# design.net
KiCad netlist of a schematic drawn in Altium Designer
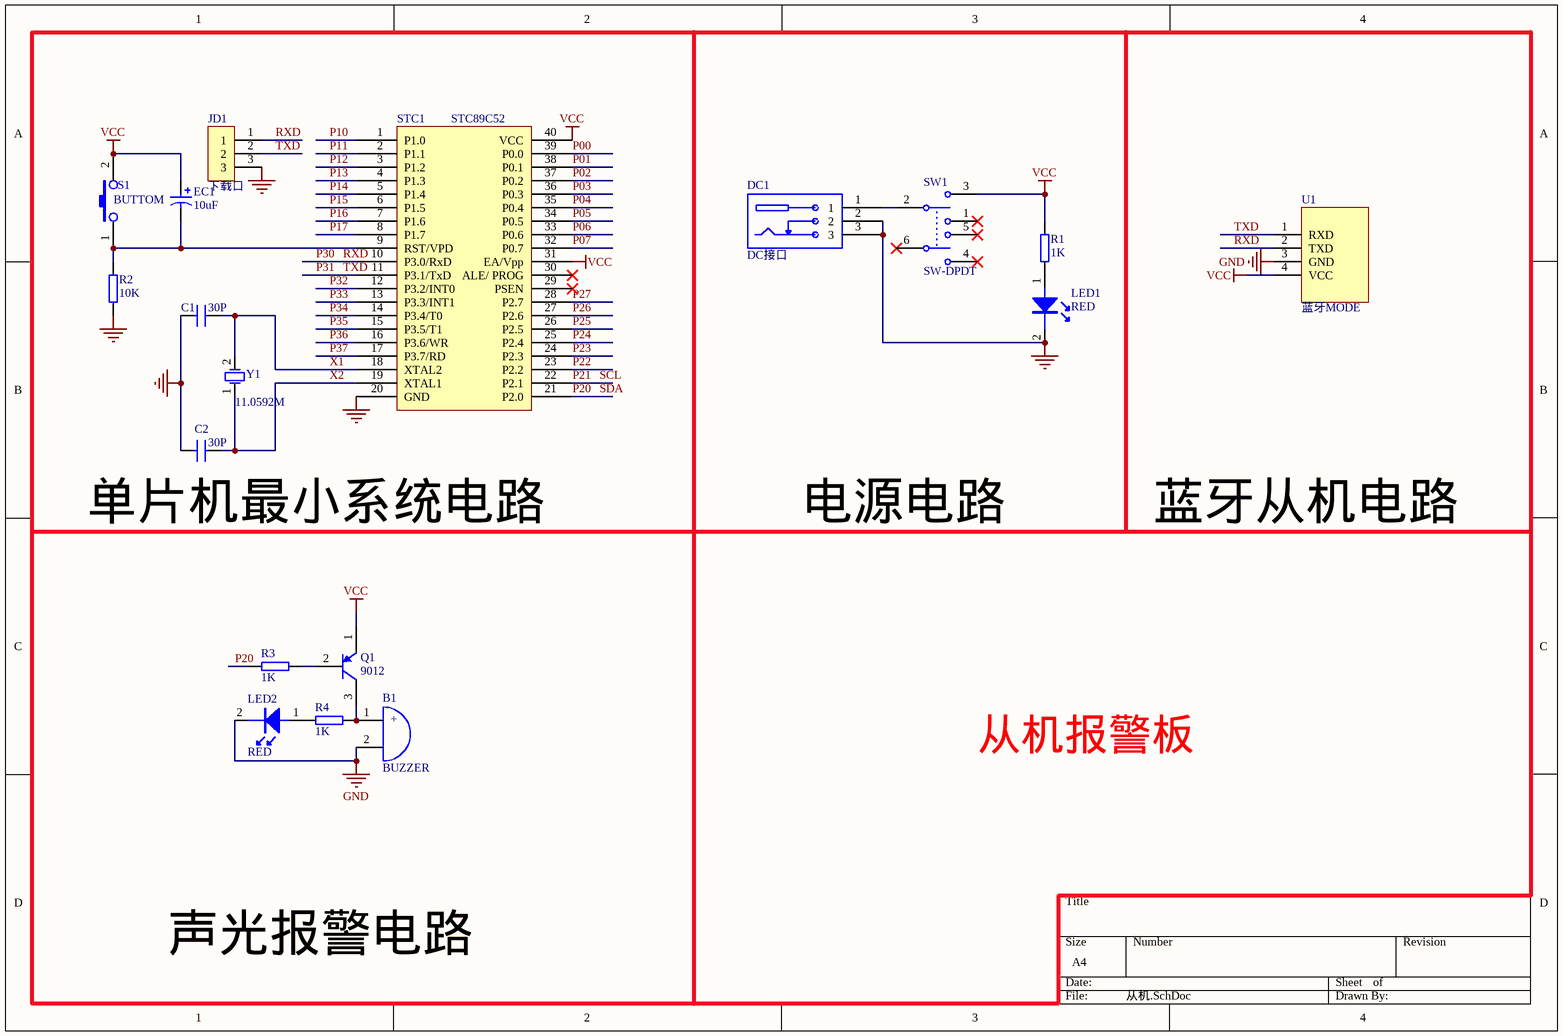
[diagram p0: 从机.SchDoc]

(export (version "E")
  (design (tool "Eeschema 10.0.6"))
  (components
    (comp (ref "B1")
      (value "BUZZER")
      (footprint "BUZZERSOT_PLASTIC")
      (description "蜂鸣器")
      (libsource (lib "参考") (part "BUZZER"))
    )
    (comp (ref "C1")
      (value "30P")
      (footprint "RAD-0.1")
      (description "无极性电容")
      (libsource (lib "参考") (part "CAP"))
    )
    (comp (ref "C2")
      (value "30P")
      (footprint "RAD-0.1")
      (description "无极性电容")
      (libsource (lib "参考") (part "CAP"))
    )
    (comp (ref "DC1")
      (value "DC接口")
      (footprint "DC-JACK-002")
      (description "DC接口（分大小）")
      (libsource (lib "参考") (part "DC接口"))
    )
    (comp (ref "EC1")
      (value "10uF")
      (footprint "RB.1/.2")
      (description "极性电容")
      (libsource (lib "参考") (part "CAP_EC"))
    )
    (comp (ref "JD1")
      (value "下载口")
      (footprint "下载串口")
      (description "下载口2.54排针")
      (libsource (lib "参考") (part "下载口"))
    )
    (comp (ref "LED1")
      (value "RED")
      (footprint "LED_D3MM12")
      (description "LED灯")
      (libsource (lib "参考") (part "LED"))
    )
    (comp (ref "LED2")
      (value "RED")
      (footprint "LED_D3MM12")
      (description "LED灯")
      (libsource (lib "参考") (part "LED"))
    )
    (comp (ref "Q1")
      (value "9012")
      (footprint "TO-92")
      (description "直插三极管")
      (libsource (lib "参考") (part "9012"))
    )
    (comp (ref "R1")
      (value "1K")
      (footprint "AXIAL0.3")
      (description "电阻")
      (libsource (lib "参考") (part "RES"))
    )
    (comp (ref "R2")
      (value "10K")
      (footprint "AXIAL0.3")
      (description "电阻")
      (libsource (lib "参考") (part "RES"))
    )
    (comp (ref "R3")
      (value "1K")
      (footprint "AXIAL0.3")
      (description "电阻")
      (libsource (lib "参考") (part "RES"))
    )
    (comp (ref "R4")
      (value "1K")
      (footprint "AXIAL0.3")
      (description "电阻")
      (libsource (lib "参考") (part "RES"))
    )
    (comp (ref "S1")
      (value "BUTTOM")
      (footprint "BUTTOM_6x6DIP")
      (description "按键")
      (libsource (lib "参考") (part "BUTTOM"))
    )
    (comp (ref "STC1")
      (value "STC89C52")
      (footprint "STC89")
      (description "51单片机")
      (libsource (lib "参考") (part "STC51"))
    )
    (comp (ref "SW1")
      (value "SW-DPDT")
      (footprint "SW")
      (description "电源开关")
      (fields (field (name "PUBLISHER") "Altium Limited"))
      (libsource (lib "参考") (part "SW-DPDT"))
    )
    (comp (ref "U1")
      (value "蓝牙MODE")
      (footprint "蓝牙MODE平放")
      (description "蓝牙模块")
      (libsource (lib "参考") (part "蓝牙MODE"))
    )
    (comp (ref "Y1")
      (value "11.0592M")
      (footprint "X_HC-49")
      (description "晶振")
      (libsource (lib "参考") (part "XTAL DIP"))
    )
  )
  (nets
    (net (code "1") (name "/P00") (class "Default")
      (node (ref "STC1") (pin "39") (pinfunction "P0.0_39") (pintype "passive"))
    )
    (net (code "2") (name "/P01") (class "Default")
      (node (ref "STC1") (pin "38") (pinfunction "P0.1_38") (pintype "passive"))
    )
    (net (code "3") (name "/P02") (class "Default")
      (node (ref "STC1") (pin "37") (pinfunction "P0.2_37") (pintype "passive"))
    )
    (net (code "4") (name "/P03") (class "Default")
      (node (ref "STC1") (pin "36") (pinfunction "P0.3_36") (pintype "passive"))
    )
    (net (code "5") (name "/P04") (class "Default")
      (node (ref "STC1") (pin "35") (pinfunction "P0.4_35") (pintype "passive"))
    )
    (net (code "6") (name "/P05") (class "Default")
      (node (ref "STC1") (pin "34") (pinfunction "P0.5_34") (pintype "passive"))
    )
    (net (code "7") (name "/P06") (class "Default")
      (node (ref "STC1") (pin "33") (pinfunction "P0.6_33") (pintype "passive"))
    )
    (net (code "8") (name "/P07") (class "Default")
      (node (ref "STC1") (pin "32") (pinfunction "P0.7_32") (pintype "passive"))
    )
    (net (code "9") (name "/P10") (class "Default")
      (node (ref "STC1") (pin "1") (pinfunction "P1.0_1") (pintype "passive"))
    )
    (net (code "10") (name "/P11") (class "Default")
      (node (ref "STC1") (pin "2") (pinfunction "P1.1_2") (pintype "passive"))
    )
    (net (code "11") (name "/P12") (class "Default")
      (node (ref "STC1") (pin "3") (pinfunction "P1.2_3") (pintype "passive"))
    )
    (net (code "12") (name "/P13") (class "Default")
      (node (ref "STC1") (pin "4") (pinfunction "P1.3_4") (pintype "passive"))
    )
    (net (code "13") (name "/P14") (class "Default")
      (node (ref "STC1") (pin "5") (pinfunction "P1.4_5") (pintype "passive"))
    )
    (net (code "14") (name "/P15") (class "Default")
      (node (ref "STC1") (pin "6") (pinfunction "P1.5_6") (pintype "passive"))
    )
    (net (code "15") (name "/P16") (class "Default")
      (node (ref "STC1") (pin "7") (pinfunction "P1.6_7") (pintype "passive"))
    )
    (net (code "16") (name "/P17") (class "Default")
      (node (ref "STC1") (pin "8") (pinfunction "P1.7_8") (pintype "passive"))
    )
    (net (code "17") (name "/P20") (class "Default")
      (node (ref "R3") (pin "2") (pinfunction "2_2") (pintype "passive"))
      (node (ref "STC1") (pin "21") (pinfunction "P2.0_21") (pintype "passive"))
    )
    (net (code "18") (name "/P21") (class "Default")
      (node (ref "STC1") (pin "22") (pinfunction "P2.1_22") (pintype "passive"))
    )
    (net (code "19") (name "/P22") (class "Default")
      (node (ref "STC1") (pin "23") (pinfunction "P2.2_23") (pintype "passive"))
    )
    (net (code "20") (name "/P23") (class "Default")
      (node (ref "STC1") (pin "24") (pinfunction "P2.3_24") (pintype "passive"))
    )
    (net (code "21") (name "/P24") (class "Default")
      (node (ref "STC1") (pin "25") (pinfunction "P2.4_25") (pintype "passive"))
    )
    (net (code "22") (name "/P25") (class "Default")
      (node (ref "STC1") (pin "26") (pinfunction "P2.5_26") (pintype "passive"))
    )
    (net (code "23") (name "/P26") (class "Default")
      (node (ref "STC1") (pin "27") (pinfunction "P2.6_27") (pintype "passive"))
    )
    (net (code "24") (name "/P27") (class "Default")
      (node (ref "STC1") (pin "28") (pinfunction "P2.7_28") (pintype "passive"))
    )
    (net (code "25") (name "/P30") (class "Default")
      (node (ref "JD1") (pin "1") (pinfunction "1_1") (pintype "passive"))
      (node (ref "STC1") (pin "10") (pinfunction "P3.0/RxD_10") (pintype "passive"))
      (node (ref "U1") (pin "2") (pinfunction "TXD_2") (pintype "passive"))
    )
    (net (code "26") (name "/P31") (class "Default")
      (node (ref "JD1") (pin "2") (pinfunction "2_2") (pintype "passive"))
      (node (ref "STC1") (pin "11") (pinfunction "P3.1/TxD_11") (pintype "passive"))
      (node (ref "U1") (pin "1") (pinfunction "RXD_1") (pintype "passive"))
    )
    (net (code "27") (name "/P32") (class "Default")
      (node (ref "STC1") (pin "12") (pinfunction "P3.2/INT0_12") (pintype "passive"))
    )
    (net (code "28") (name "/P33") (class "Default")
      (node (ref "STC1") (pin "13") (pinfunction "P3.3/INT1_13") (pintype "passive"))
    )
    (net (code "29") (name "/P34") (class "Default")
      (node (ref "STC1") (pin "14") (pinfunction "P3.4/T0_14") (pintype "passive"))
    )
    (net (code "30") (name "/P35") (class "Default")
      (node (ref "STC1") (pin "15") (pinfunction "P3.5/T1_15") (pintype "passive"))
    )
    (net (code "31") (name "/P36") (class "Default")
      (node (ref "STC1") (pin "16") (pinfunction "P3.6/WR_16") (pintype "passive"))
    )
    (net (code "32") (name "/P37") (class "Default")
      (node (ref "STC1") (pin "17") (pinfunction "P3.7/RD_17") (pintype "passive"))
    )
    (net (code "33") (name "/X1") (class "Default")
      (node (ref "C1") (pin "2") (pinfunction "2_2") (pintype "passive"))
      (node (ref "STC1") (pin "18") (pinfunction "XTAL2_18") (pintype "passive"))
      (node (ref "Y1") (pin "2") (pinfunction "OSC2_2") (pintype "passive"))
    )
    (net (code "34") (name "/X2") (class "Default")
      (node (ref "C2") (pin "2") (pinfunction "2_2") (pintype "passive"))
      (node (ref "STC1") (pin "19") (pinfunction "XTAL1_19") (pintype "passive"))
      (node (ref "Y1") (pin "1") (pinfunction "OSC1_1") (pintype "passive"))
    )
    (net (code "35") (name "GND") (class "Default")
      (node (ref "B1") (pin "2") (pinfunction "2_2") (pintype "passive"))
      (node (ref "C1") (pin "1") (pinfunction "1_1") (pintype "passive"))
      (node (ref "C2") (pin "1") (pinfunction "1_1") (pintype "passive"))
      (node (ref "DC1") (pin "2") (pinfunction "2_2") (pintype "passive"))
      (node (ref "DC1") (pin "3") (pinfunction "3_3") (pintype "passive"))
      (node (ref "JD1") (pin "3") (pinfunction "3_3") (pintype "passive"))
      (node (ref "LED1") (pin "2") (pinfunction "2_2") (pintype "passive"))
      (node (ref "LED2") (pin "2") (pinfunction "2_2") (pintype "passive"))
      (node (ref "R2") (pin "1") (pinfunction "1_1") (pintype "passive"))
      (node (ref "STC1") (pin "20") (pinfunction "GND_20") (pintype "passive"))
      (node (ref "U1") (pin "3") (pinfunction "GND_3") (pintype "passive"))
    )
    (net (code "36") (name "Net-(DC1-Pad1)") (class "Default")
      (node (ref "DC1") (pin "1") (pinfunction "1_1") (pintype "passive"))
      (node (ref "SW1") (pin "2") (pinfunction "2_2") (pintype "passive"))
    )
    (net (code "37") (name "Net-(LED1-Pad1)") (class "Default")
      (node (ref "LED1") (pin "1") (pinfunction "1_1") (pintype "passive"))
      (node (ref "R1") (pin "1") (pinfunction "1_1") (pintype "passive"))
    )
    (net (code "38") (name "Net-(LED2-Pad1)") (class "Default")
      (node (ref "LED2") (pin "1") (pinfunction "1_1") (pintype "passive"))
      (node (ref "R4") (pin "1") (pinfunction "1_1") (pintype "passive"))
    )
    (net (code "39") (name "Net-(Q1-b)") (class "Default")
      (node (ref "Q1") (pin "2") (pinfunction "b_2") (pintype "passive"))
      (node (ref "R3") (pin "1") (pinfunction "1_1") (pintype "passive"))
    )
    (net (code "40") (name "Net-(Q1-c)") (class "Default")
      (node (ref "B1") (pin "1") (pinfunction "1_1") (pintype "passive"))
      (node (ref "Q1") (pin "3") (pinfunction "c_3") (pintype "passive"))
      (node (ref "R4") (pin "2") (pinfunction "2_2") (pintype "passive"))
    )
    (net (code "41") (name "Net-(STC1-RST{slash}VPD)") (class "Default")
      (node (ref "EC1") (pin "2") (pinfunction "2_2") (pintype "passive"))
      (node (ref "R2") (pin "2") (pinfunction "2_2") (pintype "passive"))
      (node (ref "S1") (pin "1") (pinfunction "1_1") (pintype "passive"))
      (node (ref "STC1") (pin "9") (pinfunction "RST/VPD_9") (pintype "passive"))
    )
    (net (code "42") (name "VCC") (class "Default")
      (node (ref "EC1") (pin "1") (pinfunction "1_1") (pintype "passive"))
      (node (ref "Q1") (pin "1") (pinfunction "e_1") (pintype "passive"))
      (node (ref "R1") (pin "2") (pinfunction "2_2") (pintype "passive"))
      (node (ref "S1") (pin "2") (pinfunction "2_2") (pintype "passive"))
      (node (ref "STC1") (pin "31") (pinfunction "EA/Vpp_31") (pintype "passive"))
      (node (ref "STC1") (pin "40") (pinfunction "VCC_40") (pintype "passive"))
      (node (ref "SW1") (pin "3") (pinfunction "3_3") (pintype "passive"))
      (node (ref "U1") (pin "4") (pinfunction "VCC_4") (pintype "passive"))
    )
    (net (code "43") (name "unconnected-(STC1-ALE{slash}_PROG-Pad30)") (class "Default")
      (node (ref "STC1") (pin "30") (pinfunction "ALE/_PROG_30") (pintype "passive+no_connect"))
    )
    (net (code "44") (name "unconnected-(STC1-PSEN-Pad29)") (class "Default")
      (node (ref "STC1") (pin "29") (pinfunction "PSEN_29") (pintype "passive+no_connect"))
    )
    (net (code "45") (name "unconnected-(SW1-Pad1)") (class "Default")
      (node (ref "SW1") (pin "1") (pinfunction "1_1") (pintype "passive+no_connect"))
    )
    (net (code "46") (name "unconnected-(SW1-Pad4)") (class "Default")
      (node (ref "SW1") (pin "4") (pinfunction "4_4") (pintype "passive+no_connect"))
    )
    (net (code "47") (name "unconnected-(SW1-Pad5)") (class "Default")
      (node (ref "SW1") (pin "5") (pinfunction "5_5") (pintype "passive+no_connect"))
    )
    (net (code "48") (name "unconnected-(SW1-Pad6)") (class "Default")
      (node (ref "SW1") (pin "6") (pinfunction "6_6") (pintype "passive+no_connect"))
    )
  )
)
